# ASD2431.net
KiCad netlist of a schematic drawn in EAGLE
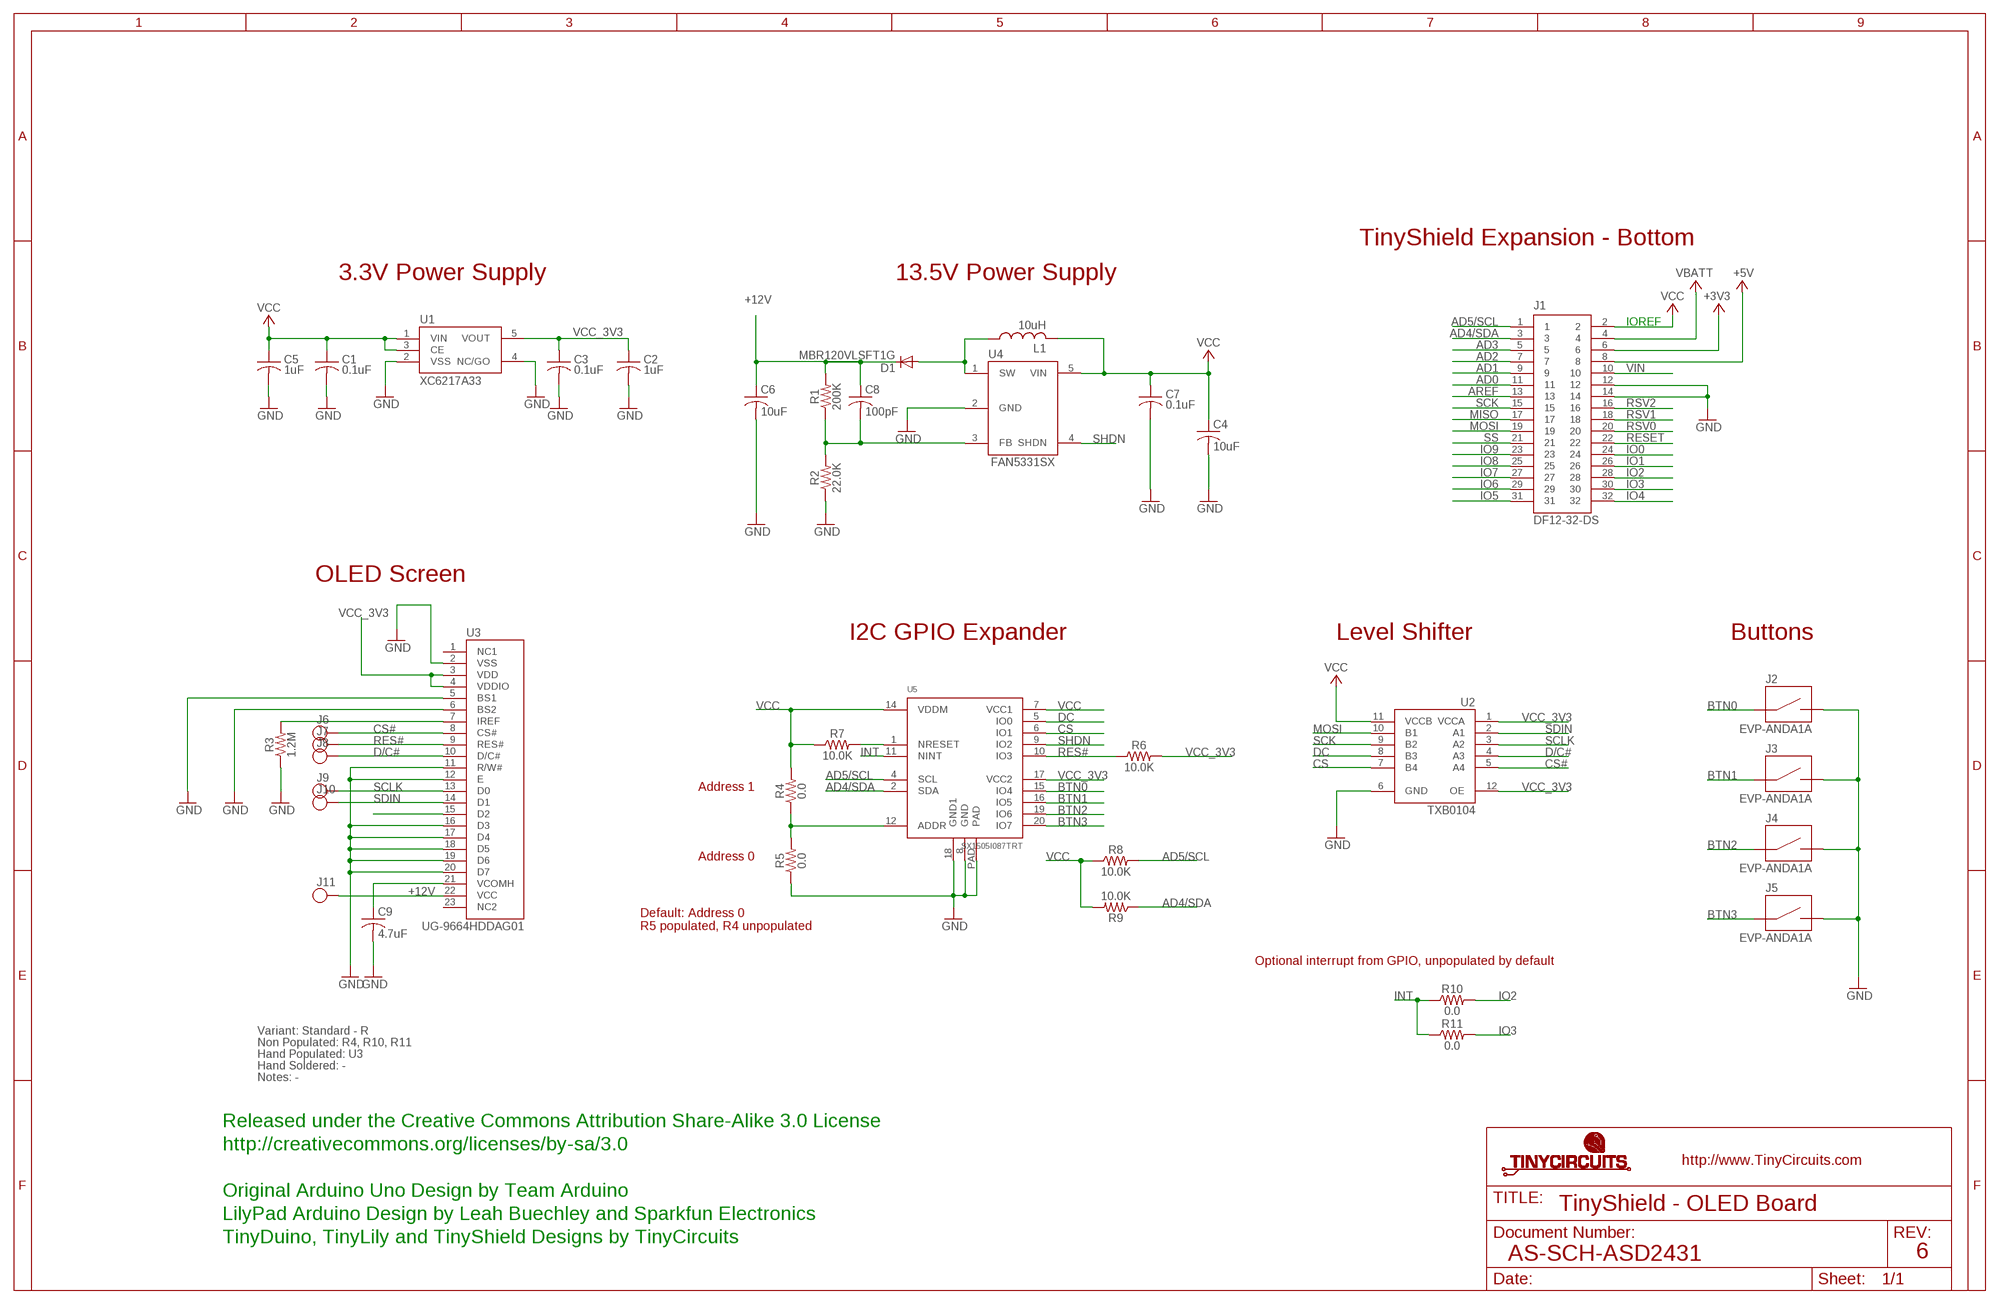
[diagram p0: schematic, sheet 1]

(export (version "E")
  (design (tool "Eeschema 10.0.6"))
  (components
    (comp (ref "C1")
      (value "0.1uF")
      (footprint "eagle-import:C0402")
      (fields (field (name "PARTNO") "AS-ITM-00008") (field (name "PARTNO_1") "AS-ITM-00008"))
      (libsource (lib "eagle-import") (part "AS-ITM-00008"))
    )
    (comp (ref "C2")
      (value "1uF")
      (footprint "eagle-import:C0402")
      (fields (field (name "PARTNO") "AS-ITM-00105") (field (name "PARTNO_1") "AS-ITM-00105"))
      (libsource (lib "eagle-import") (part "AS-ITM-00105"))
    )
    (comp (ref "C3")
      (value "0.1uF")
      (footprint "eagle-import:C0402")
      (fields (field (name "PARTNO") "AS-ITM-00008") (field (name "PARTNO_1") "AS-ITM-00008"))
      (libsource (lib "eagle-import") (part "AS-ITM-00008"))
    )
    (comp (ref "C4")
      (value "10uF")
      (footprint "eagle-import:C0805")
      (fields (field (name "PARTNO") "AS-ITM-00045") (field (name "PARTNO_1") "AS-ITM-00045"))
      (libsource (lib "eagle-import") (part "AS-ITM-00045"))
    )
    (comp (ref "C5")
      (value "1uF")
      (footprint "eagle-import:C0402")
      (fields (field (name "PARTNO") "AS-ITM-00105") (field (name "PARTNO_1") "AS-ITM-00105"))
      (libsource (lib "eagle-import") (part "AS-ITM-00105"))
    )
    (comp (ref "C6")
      (value "10uF")
      (footprint "eagle-import:C0805")
      (fields (field (name "PARTNO") "AS-ITM-00045") (field (name "PARTNO_1") "AS-ITM-00045"))
      (libsource (lib "eagle-import") (part "AS-ITM-00045"))
    )
    (comp (ref "C7")
      (value "0.1uF")
      (footprint "eagle-import:C0402")
      (fields (field (name "PARTNO") "AS-ITM-00008") (field (name "PARTNO_1") "AS-ITM-00008"))
      (libsource (lib "eagle-import") (part "AS-ITM-00008"))
    )
    (comp (ref "C8")
      (value "100pF")
      (footprint "eagle-import:0402")
      (fields (field (name "PARTNO") "AS-ITM-00148") (field (name "PARTNO_1") "AS-ITM-00148"))
      (libsource (lib "eagle-import") (part "AS-ITM-00148"))
    )
    (comp (ref "C9")
      (value "4.7uF")
      (footprint "eagle-import:1206_CAP_TANT")
      (fields (field (name "PARTNO") "AS-ITM-00232") (field (name "PARTNO_1") "AS-ITM-00232"))
      (libsource (lib "eagle-import") (part "AS-ITM-00232"))
    )
    (comp (ref "D1")
      (value "MBR120VLSFT1G")
      (footprint "eagle-import:SOD-123FL")
      (fields (field (name "PARTNO") "AS-ITM-00111"))
      (libsource (lib "eagle-import") (part "AS-ITM-00111"))
    )
    (comp (ref "J1")
      (value "DF12-32-DS")
      (footprint "eagle-import:DF12-32-DS")
      (fields (field (name "PARTNO") "AS-ITM-00012") (field (name "PARTNO_1") "AS-ITM-00012"))
      (libsource (lib "eagle-import") (part "AS-ITM-00012"))
    )
    (comp (ref "J2")
      (value "EVP-ANDA1A")
      (footprint "eagle-import:PTS840GKP")
      (fields (field (name "PARTNO") "AS-ITM-00236") (field (name "PARTNO_1") "AS-ITM-00236"))
      (libsource (lib "eagle-import") (part "AS-ITM-00236"))
    )
    (comp (ref "J3")
      (value "EVP-ANDA1A")
      (footprint "eagle-import:PTS840GKP")
      (fields (field (name "PARTNO") "AS-ITM-00236") (field (name "PARTNO_1") "AS-ITM-00236"))
      (libsource (lib "eagle-import") (part "AS-ITM-00236"))
    )
    (comp (ref "J4")
      (value "EVP-ANDA1A")
      (footprint "eagle-import:PTS840GKP")
      (fields (field (name "PARTNO") "AS-ITM-00236") (field (name "PARTNO_1") "AS-ITM-00236"))
      (libsource (lib "eagle-import") (part "AS-ITM-00236"))
    )
    (comp (ref "J5")
      (value "EVP-ANDA1A")
      (footprint "eagle-import:PTS840GKP")
      (fields (field (name "PARTNO") "AS-ITM-00236") (field (name "PARTNO_1") "AS-ITM-00236"))
      (libsource (lib "eagle-import") (part "AS-ITM-00236"))
    )
    (comp (ref "J6")
      (value "TEST_POINT")
      (footprint "eagle-import:TEST_POINT_1MM")
      (libsource (lib "eagle-import") (part "TEST_POINT"))
    )
    (comp (ref "J7")
      (value "TEST_POINT")
      (footprint "eagle-import:TEST_POINT_1MM")
      (libsource (lib "eagle-import") (part "TEST_POINT"))
    )
    (comp (ref "J8")
      (value "TEST_POINT")
      (footprint "eagle-import:TEST_POINT_1MM")
      (libsource (lib "eagle-import") (part "TEST_POINT"))
    )
    (comp (ref "J9")
      (value "TEST_POINT")
      (footprint "eagle-import:TEST_POINT_1MM")
      (libsource (lib "eagle-import") (part "TEST_POINT"))
    )
    (comp (ref "J10")
      (value "TEST_POINT")
      (footprint "eagle-import:TEST_POINT_1MM")
      (libsource (lib "eagle-import") (part "TEST_POINT"))
    )
    (comp (ref "J11")
      (value "TEST_POINT")
      (footprint "eagle-import:TEST_POINT_1MM")
      (libsource (lib "eagle-import") (part "TEST_POINT"))
    )
    (comp (ref "L1")
      (value "10uH")
      (footprint "eagle-import:R0805")
      (fields (field (name "PARTNO") "AS-ITM-00165"))
      (libsource (lib "eagle-import") (part "AS-ITM-00165"))
    )
    (comp (ref "R1")
      (value "200K")
      (footprint "eagle-import:0402")
      (fields (field (name "PARTNO") "AS-ITM-00178") (field (name "PARTNO_1") "AS-ITM-00178"))
      (libsource (lib "eagle-import") (part "AS-ITM-00178"))
    )
    (comp (ref "R2")
      (value "22.0K")
      (footprint "eagle-import:0402")
      (fields (field (name "PARTNO") "AS-ITM-00147") (field (name "PARTNO_1") "AS-ITM-00147"))
      (libsource (lib "eagle-import") (part "AS-ITM-00147"))
    )
    (comp (ref "R3")
      (value "1.2M")
      (footprint "eagle-import:0402")
      (fields (field (name "PARTNO") "AS-ITM-00280") (field (name "PARTNO_1") "AS-ITM-00280"))
      (libsource (lib "eagle-import") (part "AS-ITM-00280"))
    )
    (comp (ref "R4")
      (value "0.0")
      (footprint "eagle-import:0402")
      (fields (field (name "PARTNO") "AS-ITM-00076"))
      (libsource (lib "eagle-import") (part "AS-ITM-00076"))
    )
    (comp (ref "R5")
      (value "0.0")
      (footprint "eagle-import:0402")
      (fields (field (name "PARTNO") "AS-ITM-00076"))
      (libsource (lib "eagle-import") (part "AS-ITM-00076"))
    )
    (comp (ref "R6")
      (value "10.0K")
      (footprint "eagle-import:0402")
      (fields (field (name "PARTNO") "AS-ITM-00032"))
      (libsource (lib "eagle-import") (part "AS-ITM-00032"))
    )
    (comp (ref "R7")
      (value "10.0K")
      (footprint "eagle-import:0402")
      (fields (field (name "PARTNO") "AS-ITM-00032") (field (name "PARTNO_1") "AS-ITM-00032"))
      (libsource (lib "eagle-import") (part "AS-ITM-00032"))
    )
    (comp (ref "R8")
      (value "10.0K")
      (footprint "eagle-import:0402")
      (fields (field (name "PARTNO") "AS-ITM-00032") (field (name "PARTNO_1") "AS-ITM-00032"))
      (libsource (lib "eagle-import") (part "AS-ITM-00032"))
    )
    (comp (ref "R9")
      (value "10.0K")
      (footprint "eagle-import:0402")
      (fields (field (name "PARTNO") "AS-ITM-00032") (field (name "PARTNO_1") "AS-ITM-00032"))
      (libsource (lib "eagle-import") (part "AS-ITM-00032"))
    )
    (comp (ref "R10")
      (value "0.0")
      (footprint "eagle-import:0402")
      (fields (field (name "PARTNO") "AS-ITM-00076") (field (name "PARTNO_1") "AS-ITM-00076"))
      (libsource (lib "eagle-import") (part "AS-ITM-00076"))
    )
    (comp (ref "R11")
      (value "0.0")
      (footprint "eagle-import:0402")
      (fields (field (name "PARTNO") "AS-ITM-00076") (field (name "PARTNO_1") "AS-ITM-00076"))
      (libsource (lib "eagle-import") (part "AS-ITM-00076"))
    )
    (comp (ref "U1")
      (value "XC6217A33")
      (footprint "eagle-import:SOT-25")
      (fields (field (name "PARTNO") "AS-ITM-00249") (field (name "PARTNO_1") "AS-ITM-00249"))
      (libsource (lib "eagle-import") (part "AS-ITM-00249"))
    )
    (comp (ref "U2")
      (value "TXB0104")
      (footprint "eagle-import:UQFN-12")
      (fields (field (name "PARTNO") "AS-ITM-00048"))
      (libsource (lib "eagle-import") (part "AS-ITM-00048"))
    )
    (comp (ref "U3")
      (value "UG-9664HDDAG01")
      (footprint "eagle-import:OLED_DISPLAY")
      (fields (field (name "PARTNO") "AS-ITM-00158"))
      (libsource (lib "eagle-import") (part "AS-ITM-00158"))
    )
    (comp (ref "U4")
      (value "FAN5331SX")
      (footprint "eagle-import:SOT-23")
      (fields (field (name "PARTNO") "AS-ITM-00163"))
      (libsource (lib "eagle-import") (part "AS-ITM-00163"))
    )
    (comp (ref "U5")
      (value "SX1505I087TRT")
      (footprint "eagle-import:QFN-UT20")
      (fields (field (name "PARTNO") "AS-ITM-00203"))
      (libsource (lib "eagle-import") (part "AS-ITM-00203"))
    )
  )
  (nets
    (net (code "1") (name "+3V3") (class "Default")
      (node (ref "J1") (pin "6") (pinfunction "6_6") (pintype "bidirectional"))
    )
    (net (code "2") (name "+5V") (class "Default")
      (node (ref "J1") (pin "8") (pinfunction "8_8") (pintype "bidirectional"))
    )
    (net (code "3") (name "/+12V") (class "Default")
      (node (ref "C6") (pin "1") (pinfunction "1_1") (pintype "passive"))
      (node (ref "C8") (pin "1") (pinfunction "1_1") (pintype "passive"))
      (node (ref "D1") (pin "C") (pinfunction "C_C") (pintype "passive"))
      (node (ref "J11") (pin "P$1") (pinfunction "1_P$1") (pintype "bidirectional"))
      (node (ref "R1") (pin "2") (pinfunction "2_2") (pintype "passive"))
      (node (ref "U3") (pin "22") (pinfunction "VCC_22") (pintype "bidirectional"))
    )
    (net (code "4") (name "/AD0") (class "Default")
      (node (ref "J1") (pin "11") (pinfunction "11_11") (pintype "bidirectional"))
    )
    (net (code "5") (name "/AD1") (class "Default")
      (node (ref "J1") (pin "9") (pinfunction "9_9") (pintype "bidirectional"))
    )
    (net (code "6") (name "/AD2") (class "Default")
      (node (ref "J1") (pin "7") (pinfunction "7_7") (pintype "bidirectional"))
    )
    (net (code "7") (name "/AD3") (class "Default")
      (node (ref "J1") (pin "5") (pinfunction "5_5") (pintype "bidirectional"))
    )
    (net (code "8") (name "/AD4{slash}SDA") (class "Default")
      (node (ref "J1") (pin "3") (pinfunction "3_3") (pintype "bidirectional"))
      (node (ref "R9") (pin "1") (pinfunction "1_1") (pintype "passive"))
      (node (ref "U5") (pin "2") (pinfunction "SDA_2") (pintype "bidirectional"))
    )
    (net (code "9") (name "/AD5{slash}SCL") (class "Default")
      (node (ref "J1") (pin "1") (pinfunction "1_1") (pintype "bidirectional"))
      (node (ref "R8") (pin "2") (pinfunction "2_2") (pintype "passive"))
      (node (ref "U5") (pin "4") (pinfunction "SCL_4") (pintype "bidirectional"))
    )
    (net (code "10") (name "/AREF") (class "Default")
      (node (ref "J1") (pin "13") (pinfunction "13_13") (pintype "bidirectional"))
    )
    (net (code "11") (name "/BTN0") (class "Default")
      (node (ref "J2") (pin "1") (pinfunction "1_1") (pintype "bidirectional"))
      (node (ref "J2") (pin "2") (pinfunction "1_2") (pintype "bidirectional"))
      (node (ref "U5") (pin "15") (pinfunction "IO4_15") (pintype "bidirectional"))
    )
    (net (code "12") (name "/BTN1") (class "Default")
      (node (ref "J3") (pin "1") (pinfunction "1_1") (pintype "bidirectional"))
      (node (ref "J3") (pin "2") (pinfunction "1_2") (pintype "bidirectional"))
      (node (ref "U5") (pin "16") (pinfunction "IO5_16") (pintype "bidirectional"))
    )
    (net (code "13") (name "/BTN2") (class "Default")
      (node (ref "J4") (pin "1") (pinfunction "1_1") (pintype "bidirectional"))
      (node (ref "J4") (pin "2") (pinfunction "1_2") (pintype "bidirectional"))
      (node (ref "U5") (pin "19") (pinfunction "IO6_19") (pintype "bidirectional"))
    )
    (net (code "14") (name "/BTN3") (class "Default")
      (node (ref "J5") (pin "1") (pinfunction "1_1") (pintype "bidirectional"))
      (node (ref "J5") (pin "2") (pinfunction "1_2") (pintype "bidirectional"))
      (node (ref "U5") (pin "20") (pinfunction "IO7_20") (pintype "bidirectional"))
    )
    (net (code "15") (name "/CS") (class "Default")
      (node (ref "U2") (pin "7") (pinfunction "B4_7") (pintype "bidirectional"))
      (node (ref "U5") (pin "6") (pinfunction "IO1_6") (pintype "bidirectional"))
    )
    (net (code "16") (name "/CS#") (class "Default")
      (node (ref "J6") (pin "P$1") (pinfunction "1_P$1") (pintype "bidirectional"))
      (node (ref "U2") (pin "5") (pinfunction "A4_5") (pintype "bidirectional"))
      (node (ref "U3") (pin "8") (pinfunction "CS#_8") (pintype "bidirectional"))
    )
    (net (code "17") (name "/DC") (class "Default")
      (node (ref "U2") (pin "8") (pinfunction "B3_8") (pintype "bidirectional"))
      (node (ref "U5") (pin "5") (pinfunction "IO0_5") (pintype "bidirectional"))
    )
    (net (code "18") (name "/D{slash}C#") (class "Default")
      (node (ref "J8") (pin "P$1") (pinfunction "1_P$1") (pintype "bidirectional"))
      (node (ref "U2") (pin "4") (pinfunction "A3_4") (pintype "bidirectional"))
      (node (ref "U3") (pin "10") (pinfunction "D/C#_10") (pintype "bidirectional"))
    )
    (net (code "19") (name "/INT") (class "Default")
      (node (ref "R10") (pin "1") (pinfunction "1_1") (pintype "passive"))
      (node (ref "R11") (pin "1") (pinfunction "1_1") (pintype "passive"))
      (node (ref "U5") (pin "11") (pinfunction "NINT_11") (pintype "bidirectional"))
    )
    (net (code "20") (name "/IO0") (class "Default")
      (node (ref "J1") (pin "24") (pinfunction "24_24") (pintype "bidirectional"))
    )
    (net (code "21") (name "/IO1") (class "Default")
      (node (ref "J1") (pin "26") (pinfunction "26_26") (pintype "bidirectional"))
    )
    (net (code "22") (name "/IO2") (class "Default")
      (node (ref "J1") (pin "28") (pinfunction "28_28") (pintype "bidirectional"))
      (node (ref "R10") (pin "2") (pinfunction "2_2") (pintype "passive"))
    )
    (net (code "23") (name "/IO3") (class "Default")
      (node (ref "J1") (pin "30") (pinfunction "30_30") (pintype "bidirectional"))
      (node (ref "R11") (pin "2") (pinfunction "2_2") (pintype "passive"))
    )
    (net (code "24") (name "/IO4") (class "Default")
      (node (ref "J1") (pin "32") (pinfunction "32_32") (pintype "bidirectional"))
    )
    (net (code "25") (name "/IO5") (class "Default")
      (node (ref "J1") (pin "31") (pinfunction "31_31") (pintype "bidirectional"))
    )
    (net (code "26") (name "/IO6") (class "Default")
      (node (ref "J1") (pin "29") (pinfunction "29_29") (pintype "bidirectional"))
    )
    (net (code "27") (name "/IO7") (class "Default")
      (node (ref "J1") (pin "27") (pinfunction "27_27") (pintype "bidirectional"))
    )
    (net (code "28") (name "/IO8") (class "Default")
      (node (ref "J1") (pin "25") (pinfunction "25_25") (pintype "bidirectional"))
    )
    (net (code "29") (name "/IO9") (class "Default")
      (node (ref "J1") (pin "23") (pinfunction "23_23") (pintype "bidirectional"))
    )
    (net (code "30") (name "/MISO") (class "Default")
      (node (ref "J1") (pin "17") (pinfunction "17_17") (pintype "bidirectional"))
    )
    (net (code "31") (name "/MOSI") (class "Default")
      (node (ref "J1") (pin "19") (pinfunction "19_19") (pintype "bidirectional"))
      (node (ref "U2") (pin "10") (pinfunction "B1_10") (pintype "bidirectional"))
    )
    (net (code "32") (name "/RES#") (class "Default")
      (node (ref "J7") (pin "P$1") (pinfunction "1_P$1") (pintype "bidirectional"))
      (node (ref "R6") (pin "1") (pinfunction "1_1") (pintype "passive"))
      (node (ref "U3") (pin "9") (pinfunction "RES#_9") (pintype "bidirectional"))
      (node (ref "U5") (pin "10") (pinfunction "IO3_10") (pintype "bidirectional"))
    )
    (net (code "33") (name "/RESET") (class "Default")
      (node (ref "J1") (pin "22") (pinfunction "22_22") (pintype "bidirectional"))
    )
    (net (code "34") (name "/RSV0") (class "Default")
      (node (ref "J1") (pin "20") (pinfunction "20_20") (pintype "bidirectional"))
    )
    (net (code "35") (name "/RSV1") (class "Default")
      (node (ref "J1") (pin "18") (pinfunction "18_18") (pintype "bidirectional"))
    )
    (net (code "36") (name "/RSV2") (class "Default")
      (node (ref "J1") (pin "16") (pinfunction "16_16") (pintype "bidirectional"))
    )
    (net (code "37") (name "/SCK") (class "Default")
      (node (ref "J1") (pin "15") (pinfunction "15_15") (pintype "bidirectional"))
      (node (ref "U2") (pin "9") (pinfunction "B2_9") (pintype "bidirectional"))
    )
    (net (code "38") (name "/SCLK") (class "Default")
      (node (ref "J9") (pin "P$1") (pinfunction "1_P$1") (pintype "bidirectional"))
      (node (ref "U2") (pin "3") (pinfunction "A2_3") (pintype "bidirectional"))
      (node (ref "U3") (pin "13") (pinfunction "D0_13") (pintype "bidirectional"))
    )
    (net (code "39") (name "/SDIN") (class "Default")
      (node (ref "J10") (pin "P$1") (pinfunction "1_P$1") (pintype "bidirectional"))
      (node (ref "U2") (pin "2") (pinfunction "A1_2") (pintype "bidirectional"))
      (node (ref "U3") (pin "14") (pinfunction "D1_14") (pintype "bidirectional"))
    )
    (net (code "40") (name "/SHDN") (class "Default")
      (node (ref "U4") (pin "4") (pinfunction "SHDN_4") (pintype "bidirectional"))
      (node (ref "U5") (pin "9") (pinfunction "IO2_9") (pintype "bidirectional"))
    )
    (net (code "41") (name "/SS") (class "Default")
      (node (ref "J1") (pin "21") (pinfunction "21_21") (pintype "bidirectional"))
    )
    (net (code "42") (name "/VCC_3V3") (class "Default")
      (node (ref "C2") (pin "1") (pinfunction "1_1") (pintype "passive"))
      (node (ref "C3") (pin "1") (pinfunction "1_1") (pintype "passive"))
      (node (ref "R6") (pin "2") (pinfunction "2_2") (pintype "passive"))
      (node (ref "U1") (pin "5") (pinfunction "VOUT_5") (pintype "bidirectional"))
      (node (ref "U2") (pin "1") (pinfunction "VCCA_1") (pintype "bidirectional"))
      (node (ref "U2") (pin "12") (pinfunction "OE_12") (pintype "bidirectional"))
      (node (ref "U3") (pin "3") (pinfunction "VDD_3") (pintype "bidirectional"))
      (node (ref "U3") (pin "4") (pinfunction "VDDIO_4") (pintype "bidirectional"))
      (node (ref "U5") (pin "17") (pinfunction "VCC2_17") (pintype "bidirectional"))
    )
    (net (code "43") (name "/VIN") (class "Default")
      (node (ref "J1") (pin "10") (pinfunction "10_10") (pintype "bidirectional"))
    )
    (net (code "44") (name "GND") (class "Default")
      (node (ref "C1") (pin "2") (pinfunction "2_2") (pintype "passive"))
      (node (ref "C2") (pin "2") (pinfunction "2_2") (pintype "passive"))
      (node (ref "C3") (pin "2") (pinfunction "2_2") (pintype "passive"))
      (node (ref "C4") (pin "2") (pinfunction "2_2") (pintype "passive"))
      (node (ref "C5") (pin "2") (pinfunction "2_2") (pintype "passive"))
      (node (ref "C6") (pin "2") (pinfunction "2_2") (pintype "passive"))
      (node (ref "C7") (pin "2") (pinfunction "2_2") (pintype "passive"))
      (node (ref "C9") (pin "2") (pinfunction "2_2") (pintype "passive"))
      (node (ref "J1") (pin "12") (pinfunction "12_12") (pintype "bidirectional"))
      (node (ref "J1") (pin "14") (pinfunction "14_14") (pintype "bidirectional"))
      (node (ref "J2") (pin "3") (pinfunction "2_3") (pintype "bidirectional"))
      (node (ref "J2") (pin "4") (pinfunction "2_4") (pintype "bidirectional"))
      (node (ref "J3") (pin "3") (pinfunction "2_3") (pintype "bidirectional"))
      (node (ref "J3") (pin "4") (pinfunction "2_4") (pintype "bidirectional"))
      (node (ref "J4") (pin "3") (pinfunction "2_3") (pintype "bidirectional"))
      (node (ref "J4") (pin "4") (pinfunction "2_4") (pintype "bidirectional"))
      (node (ref "J5") (pin "3") (pinfunction "2_3") (pintype "bidirectional"))
      (node (ref "J5") (pin "4") (pinfunction "2_4") (pintype "bidirectional"))
      (node (ref "R2") (pin "1") (pinfunction "1_1") (pintype "passive"))
      (node (ref "R3") (pin "1") (pinfunction "1_1") (pintype "passive"))
      (node (ref "R5") (pin "1") (pinfunction "1_1") (pintype "passive"))
      (node (ref "U1") (pin "2") (pinfunction "VSS_2") (pintype "power_in"))
      (node (ref "U1") (pin "4") (pinfunction "NC/GO_4") (pintype "bidirectional"))
      (node (ref "U2") (pin "6") (pinfunction "GND_6") (pintype "bidirectional"))
      (node (ref "U3") (pin "11") (pinfunction "R/W#_11") (pintype "bidirectional"))
      (node (ref "U3") (pin "12") (pinfunction "E_12") (pintype "bidirectional"))
      (node (ref "U3") (pin "16") (pinfunction "D3_16") (pintype "bidirectional"))
      (node (ref "U3") (pin "17") (pinfunction "D4_17") (pintype "bidirectional"))
      (node (ref "U3") (pin "18") (pinfunction "D5_18") (pintype "bidirectional"))
      (node (ref "U3") (pin "19") (pinfunction "D6_19") (pintype "bidirectional"))
      (node (ref "U3") (pin "2") (pinfunction "VSS_2") (pintype "bidirectional"))
      (node (ref "U3") (pin "20") (pinfunction "D7_20") (pintype "bidirectional"))
      (node (ref "U3") (pin "5") (pinfunction "BS1_5") (pintype "bidirectional"))
      (node (ref "U3") (pin "6") (pinfunction "BS2_6") (pintype "bidirectional"))
      (node (ref "U4") (pin "2") (pinfunction "GND_2") (pintype "bidirectional"))
      (node (ref "U5") (pin "18") (pinfunction "GND1_18") (pintype "bidirectional"))
      (node (ref "U5") (pin "8") (pinfunction "GND_8") (pintype "bidirectional"))
      (node (ref "U5") (pin "PAD") (pinfunction "PAD_PAD") (pintype "bidirectional"))
    )
    (net (code "45") (name "Net-(U3-IREF)") (class "Default")
      (node (ref "R3") (pin "2") (pinfunction "2_2") (pintype "passive"))
      (node (ref "U3") (pin "7") (pinfunction "IREF_7") (pintype "bidirectional"))
    )
    (net (code "46") (name "Net-(U3-VCOMH)") (class "Default")
      (node (ref "C9") (pin "1") (pinfunction "1_1") (pintype "passive"))
      (node (ref "U3") (pin "21") (pinfunction "VCOMH_21") (pintype "bidirectional"))
    )
    (net (code "47") (name "Net-(U4-FB)") (class "Default")
      (node (ref "C8") (pin "2") (pinfunction "2_2") (pintype "passive"))
      (node (ref "R1") (pin "1") (pinfunction "1_1") (pintype "passive"))
      (node (ref "R2") (pin "2") (pinfunction "2_2") (pintype "passive"))
      (node (ref "U4") (pin "3") (pinfunction "FB_3") (pintype "bidirectional"))
    )
    (net (code "48") (name "Net-(U4-SW)") (class "Default")
      (node (ref "D1") (pin "A") (pinfunction "A_A") (pintype "passive"))
      (node (ref "L1") (pin "1") (pinfunction "1_1") (pintype "passive"))
      (node (ref "U4") (pin "1") (pinfunction "SW_1") (pintype "bidirectional"))
    )
    (net (code "49") (name "Net-(U5-ADDR)") (class "Default")
      (node (ref "R4") (pin "1") (pinfunction "1_1") (pintype "passive"))
      (node (ref "R5") (pin "2") (pinfunction "2_2") (pintype "passive"))
      (node (ref "U5") (pin "12") (pinfunction "ADDR_12") (pintype "bidirectional"))
    )
    (net (code "50") (name "Net-(U5-NRESET)") (class "Default")
      (node (ref "R7") (pin "2") (pinfunction "2_2") (pintype "passive"))
      (node (ref "U5") (pin "1") (pinfunction "NRESET_1") (pintype "bidirectional"))
    )
    (net (code "51") (name "VBATT") (class "Default")
      (node (ref "J1") (pin "4") (pinfunction "4_4") (pintype "bidirectional"))
    )
    (net (code "52") (name "VCC") (class "Default")
      (node (ref "C1") (pin "1") (pinfunction "1_1") (pintype "passive"))
      (node (ref "C4") (pin "1") (pinfunction "1_1") (pintype "passive"))
      (node (ref "C5") (pin "1") (pinfunction "1_1") (pintype "passive"))
      (node (ref "C7") (pin "1") (pinfunction "1_1") (pintype "passive"))
      (node (ref "J1") (pin "2") (pinfunction "2_2") (pintype "bidirectional"))
      (node (ref "L1") (pin "2") (pinfunction "2_2") (pintype "passive"))
      (node (ref "R4") (pin "2") (pinfunction "2_2") (pintype "passive"))
      (node (ref "R7") (pin "1") (pinfunction "1_1") (pintype "passive"))
      (node (ref "R8") (pin "1") (pinfunction "1_1") (pintype "passive"))
      (node (ref "R9") (pin "2") (pinfunction "2_2") (pintype "passive"))
      (node (ref "U1") (pin "1") (pinfunction "VIN_1") (pintype "bidirectional"))
      (node (ref "U1") (pin "3") (pinfunction "CE_3") (pintype "bidirectional"))
      (node (ref "U2") (pin "11") (pinfunction "VCCB_11") (pintype "bidirectional"))
      (node (ref "U4") (pin "5") (pinfunction "VIN_5") (pintype "bidirectional"))
      (node (ref "U5") (pin "14") (pinfunction "VDDM_14") (pintype "bidirectional"))
      (node (ref "U5") (pin "7") (pinfunction "VCC1_7") (pintype "bidirectional"))
    )
    (net (code "53") (name "unconnected-(U3-D2-Pad15)") (class "Default")
      (node (ref "U3") (pin "15") (pinfunction "D2_15") (pintype "bidirectional"))
    )
    (net (code "54") (name "unconnected-(U3-NC1-Pad1)") (class "Default")
      (node (ref "U3") (pin "1") (pinfunction "NC1_1") (pintype "bidirectional"))
    )
    (net (code "55") (name "unconnected-(U3-NC2-Pad23)") (class "Default")
      (node (ref "U3") (pin "23") (pinfunction "NC2_23") (pintype "bidirectional"))
    )
  )
)
